# BopIt.net
KiCad netlist of a schematic drawn in Altium Designer
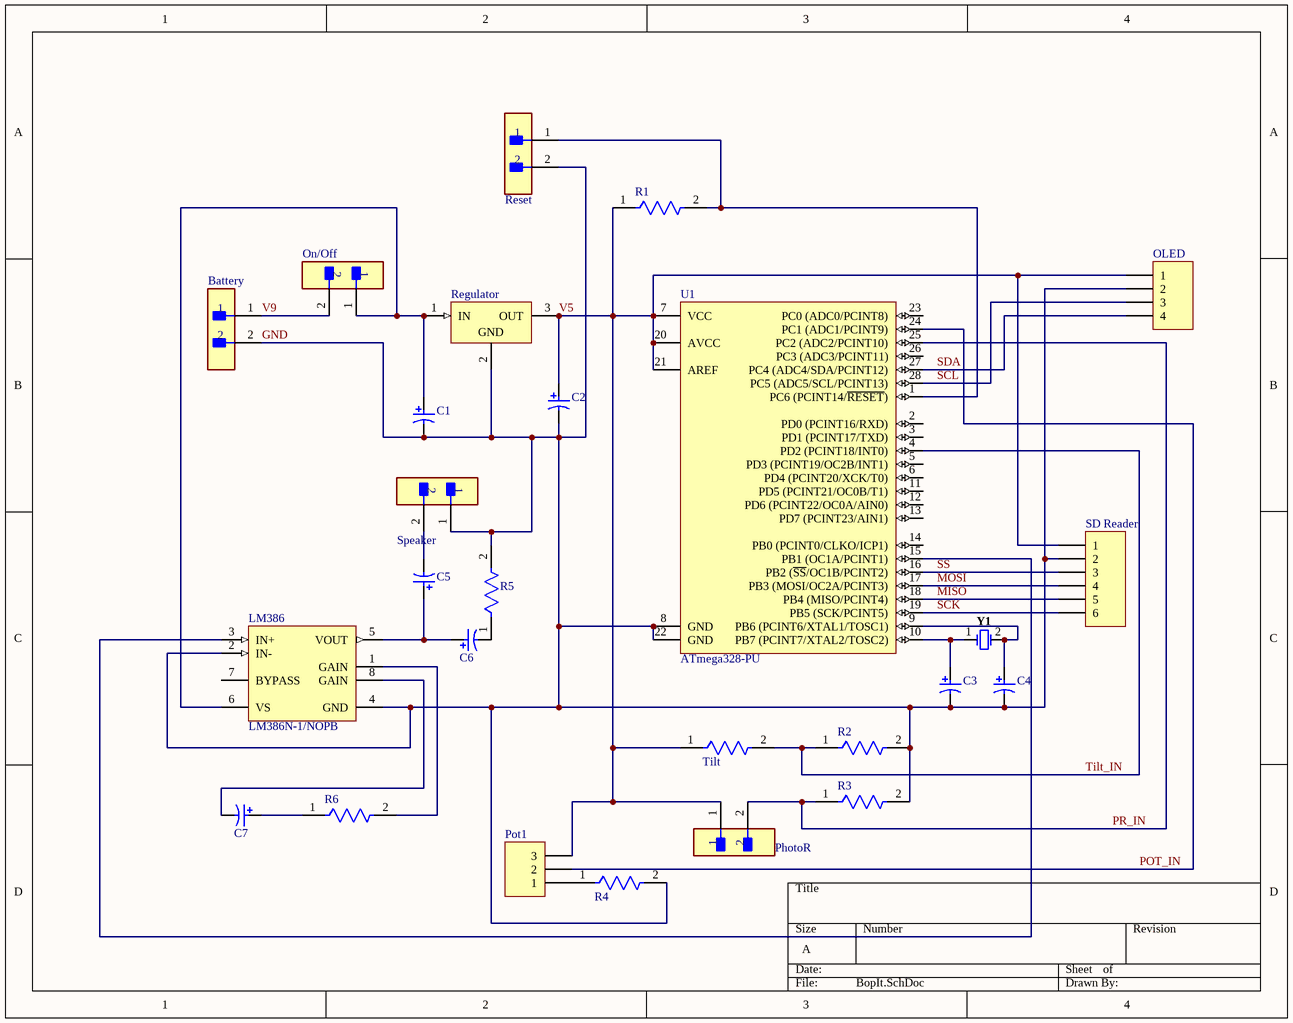
[diagram p0: BopIt.SchDoc]

(export (version "E")
  (design (tool "Eeschema 10.0.6"))
  (components
    (comp (ref "Battery")
      (value "M22-2510205")
      (footprint "FP-M22-2510205-MFG")
      (description "CONN HEADER VERT 2POS 2MM")
      (fields
        (field (name "MANUFACTURER") "Harwin")
        (field (name "OCTOPART") "https://octopart.com/m22-2510205-harwin-2538221")
      )
      (libsource (lib "") (part "3bc925449376181038e59eaffc5286c_2"))
    )
    (comp (ref "C1")
      (value "ECA1HM100")
      (footprint "CAPPR55-200-1100X500X1200")
      (description "Aluminum Electrolytic Capacitor, 10 uF, +/- 20%, 50 V, -40 to 85 degC, 2-Pin THD, RoHS, Bulk")
      (fields (field (name "MANUFACTURER") "Panasonic") (field (name "TOLERANCE") "20%"))
      (libsource (lib "Altium Content Vault") (part "CAP-P-2"))
    )
    (comp (ref "C2")
      (value "ECA1HM100")
      (footprint "CAPPR55-200-1100X500X1200")
      (description "Aluminum Electrolytic Capacitor, 10 uF, +/- 20%, 50 V, -40 to 85 degC, 2-Pin THD, RoHS, Bulk")
      (fields (field (name "MANUFACTURER") "Panasonic") (field (name "TOLERANCE") "20%"))
      (libsource (lib "Altium Content Vault") (part "CAP-P-2"))
    )
    (comp (ref "C3")
      (value "ECA1HM100")
      (footprint "CAPPR55-200-1100X500X1200")
      (description "Aluminum Electrolytic Capacitor, 10 uF, +/- 20%, 50 V, -40 to 85 degC, 2-Pin THD, RoHS, Bulk")
      (fields (field (name "MANUFACTURER") "Panasonic") (field (name "TOLERANCE") "20%"))
      (libsource (lib "Altium Content Vault") (part "CAP-P-2"))
    )
    (comp (ref "C4")
      (value "ECA1HM100")
      (footprint "CAPPR55-200-1100X500X1200")
      (description "Aluminum Electrolytic Capacitor, 10 uF, +/- 20%, 50 V, -40 to 85 degC, 2-Pin THD, RoHS, Bulk")
      (fields (field (name "MANUFACTURER") "Panasonic") (field (name "TOLERANCE") "20%"))
      (libsource (lib "Altium Content Vault") (part "CAP-P-2"))
    )
    (comp (ref "C5")
      (value "ECA-1VM221")
      (footprint "PNSC-ECA-1VM221-2")
      (description "Aluminum Electrolytic Capacitor, 220 uF, +/- 20%, 35 V, -40 to 85 degC, 2-Pin THD, RoHS, Bulk")
      (fields (field (name "MANUFACTURER") "Panasonic"))
      (libsource (lib "Altium Content Vault") (part "CAP-P-2"))
    )
    (comp (ref "C6")
      (value "ECA1HM100")
      (footprint "CAPPR55-200-1100X500X1200")
      (description "Aluminum Electrolytic Capacitor, 10 uF, +/- 20%, 50 V, -40 to 85 degC, 2-Pin THD, RoHS, Bulk")
      (fields (field (name "MANUFACTURER") "Panasonic") (field (name "TOLERANCE") "20%"))
      (libsource (lib "Altium Content Vault") (part "CAP-P-2"))
    )
    (comp (ref "C7")
      (value "ECA1HM100")
      (footprint "CAPPR55-200-1100X500X1200")
      (description "Aluminum Electrolytic Capacitor, 10 uF, +/- 20%, 50 V, -40 to 85 degC, 2-Pin THD, RoHS, Bulk")
      (fields (field (name "MANUFACTURER") "Panasonic") (field (name "TOLERANCE") "20%"))
      (libsource (lib "Altium Content Vault") (part "CAP-P-2"))
    )
    (comp (ref "LM386")
      (value "LM386N-1/NOPB")
      (footprint "P0008A")
      (description "Low Voltage Audio Power Amplifier, 8-pin MDIP, Pb-Free")
      (fields (field (name "MANUFACTURER") "Texas Instruments"))
      (libsource (lib "Altium Content Vault") (part "AMP-APA-LM386-8"))
    )
    (comp (ref "OLED")
      (value "~")
      (footprint "HDR1X4")
      (description "Header, 4-Pin")
      (fields (field (name "PUBLISHER") "Altium Limited"))
      (libsource (lib "Miscellaneous Connectors") (part "Header 4"))
    )
    (comp (ref "On/Off")
      (value "M22-2510205")
      (footprint "FP-M22-2510205-MFG")
      (description "CONN HEADER VERT 2POS 2MM")
      (fields
        (field (name "MANUFACTURER") "Harwin")
        (field (name "OCTOPART") "https://octopart.com/m22-2510205-harwin-2538221")
      )
      (libsource (lib "Altium Content Vault") (part "3bc925449376181038e59eaffc5286c"))
    )
    (comp (ref "PhotoR")
      (value "M22-2510205")
      (footprint "FP-M22-2510205-MFG")
      (description "CONN HEADER VERT 2POS 2MM")
      (fields
        (field (name "MANUFACTURER") "Harwin")
        (field (name "OCTOPART") "https://octopart.com/m22-2510205-harwin-2538221")
      )
      (libsource (lib "") (part "3bc925449376181038e59eaffc5286c_1"))
    )
    (comp (ref "Pot1")
      (value "Header 3")
      (footprint "HDR1X3")
      (description "Header, 3-Pin")
      (fields (field (name "PUBLISHER") "Altium Limited"))
      (libsource (lib "Miscellaneous Connectors") (part "Header 3"))
    )
    (comp (ref "R1")
      (value "CF18JT10K0")
      (footprint "FP-CF18-MFG")
      (description "RES 10K OHM 1/8W 5% CF AXIAL")
      (fields
        (field (name "MANUFACTURER") "Stackpole Electronics")
        (field (name "OCTOPART") "https://octopart.com/cf18jt10k0-stackpole+electronics-19205642")
      )
      (libsource (lib "Altium Content Vault") (part "1029c3af85768c4190bb7ad29bc67b5"))
    )
    (comp (ref "R2")
      (value "CF18JT10K0")
      (footprint "FP-CF18-MFG")
      (description "RES 10K OHM 1/8W 5% CF AXIAL")
      (fields
        (field (name "MANUFACTURER") "Stackpole Electronics")
        (field (name "OCTOPART") "https://octopart.com/cf18jt10k0-stackpole+electronics-19205642")
      )
      (libsource (lib "Altium Content Vault") (part "1029c3af85768c4190bb7ad29bc67b5"))
    )
    (comp (ref "R3")
      (value "CF18JT10K0")
      (footprint "FP-CF18-MFG")
      (description "RES 10K OHM 1/8W 5% CF AXIAL")
      (fields
        (field (name "MANUFACTURER") "Stackpole Electronics")
        (field (name "OCTOPART") "https://octopart.com/cf18jt10k0-stackpole+electronics-19205642")
      )
      (libsource (lib "Altium Content Vault") (part "1029c3af85768c4190bb7ad29bc67b5"))
    )
    (comp (ref "R4")
      (value "CF18JT10K0")
      (footprint "FP-CF18-MFG")
      (description "RES 10K OHM 1/8W 5% CF AXIAL")
      (fields
        (field (name "MANUFACTURER") "Stackpole Electronics")
        (field (name "OCTOPART") "https://octopart.com/cf18jt10k0-stackpole+electronics-19205642")
      )
      (libsource (lib "Altium Content Vault") (part "1029c3af85768c4190bb7ad29bc67b5"))
    )
    (comp (ref "R5")
      (value "CF18JT10K0")
      (footprint "FP-CF18-MFG")
      (description "RES 10K OHM 1/8W 5% CF AXIAL")
      (fields
        (field (name "MANUFACTURER") "Stackpole Electronics")
        (field (name "OCTOPART") "https://octopart.com/cf18jt10k0-stackpole+electronics-19205642")
      )
      (libsource (lib "Altium Content Vault") (part "1029c3af85768c4190bb7ad29bc67b5"))
    )
    (comp (ref "R6")
      (value "CF18JT10K0")
      (footprint "FP-CF18-MFG")
      (description "RES 10K OHM 1/8W 5% CF AXIAL")
      (fields
        (field (name "MANUFACTURER") "Stackpole Electronics")
        (field (name "OCTOPART") "https://octopart.com/cf18jt10k0-stackpole+electronics-19205642")
      )
      (libsource (lib "Altium Content Vault") (part "1029c3af85768c4190bb7ad29bc67b5"))
    )
    (comp (ref "Regulator")
      (value "LM7805CT")
      (footprint "FAIR-TO-220-3")
      (description "Positive Voltage Regulator, 5 V, 1 A, -40 to 125 degC, 3-Pin TO-220, RoHS, Tube")
      (fields (field (name "MANUFACTURER") "FairchildSemiconductor"))
      (libsource (lib "Altium Content Vault") (part "FAIR-LM7805CT-TO220-3"))
    )
    (comp (ref "Reset")
      (value "M22-2510205")
      (footprint "FP-M22-2510205-MFG")
      (description "CONN HEADER VERT 2POS 2MM")
      (fields
        (field (name "MANUFACTURER") "Harwin")
        (field (name "OCTOPART") "https://octopart.com/m22-2510205-harwin-2538221")
      )
      (libsource (lib "") (part "3bc925449376181038e59eaffc5286c_2"))
    )
    (comp (ref "SD Reader")
      (value "Header 6")
      (footprint "HDR1X6")
      (description "Header, 6-Pin")
      (fields (field (name "PUBLISHER") "Altium Limited"))
      (libsource (lib "Miscellaneous Connectors") (part "Header 6"))
    )
    (comp (ref "Speaker")
      (value "M22-2510205")
      (footprint "FP-M22-2510205-MFG")
      (description "CONN HEADER VERT 2POS 2MM")
      (fields
        (field (name "MANUFACTURER") "Harwin")
        (field (name "OCTOPART") "https://octopart.com/m22-2510205-harwin-2538221")
      )
      (libsource (lib "Altium Content Vault") (part "3bc925449376181038e59eaffc5286c"))
    )
    (comp (ref "Tilt")
      (value "CF18JT10K0")
      (footprint "FP-CF18-MFG")
      (description "RES 10K OHM 1/8W 5% CF AXIAL")
      (fields
        (field (name "MANUFACTURER") "Stackpole Electronics")
        (field (name "OCTOPART") "https://octopart.com/cf18jt10k0-stackpole+electronics-19205642")
      )
      (libsource (lib "Altium Content Vault") (part "1029c3af85768c4190bb7ad29bc67b5"))
    )
    (comp (ref "U1")
      (value "ATmega328-PU")
      (footprint "28P3")
      (libsource (lib "Altium Content Vault") (part "MC-8B-ATM48-IL28"))
    )
    (comp (ref "Y1")
      (value "FOXSLF/160-20")
      (footprint "FOX-FOXSLF160-20")
      (description "Resistance Weld Thru-Hole Crystal, 16 MHz, -20 to 70 degC, 2-Pin THD, RoHS, Bulk")
      (fields (field (name "TOLERANCE") "1%"))
      (libsource (lib "Altium Content Vault") (part "XTAL-1-2-2"))
    )
  )
  (nets
    (net (code "1") (name "/GND") (class "Default")
      (node (ref "Battery") (pin "2") (pinfunction "2_2") (pintype "passive"))
      (node (ref "C1") (pin "2") (pinfunction "2_2") (pintype "passive"))
      (node (ref "C2") (pin "2") (pinfunction "2_2") (pintype "passive"))
      (node (ref "C3") (pin "2") (pinfunction "2_2") (pintype "passive"))
      (node (ref "C4") (pin "2") (pinfunction "2_2") (pintype "passive"))
      (node (ref "LM386") (pin "2") (pinfunction "IN-_2") (pintype "input"))
      (node (ref "LM386") (pin "4") (pinfunction "GND_4") (pintype "power_in"))
      (node (ref "OLED") (pin "2") (pinfunction "2_2") (pintype "passive"))
      (node (ref "R2") (pin "2") (pinfunction "2_2") (pintype "passive"))
      (node (ref "R3") (pin "2") (pinfunction "2_2") (pintype "passive"))
      (node (ref "R4") (pin "2") (pinfunction "2_2") (pintype "passive"))
      (node (ref "R5") (pin "2") (pinfunction "2_2") (pintype "passive"))
      (node (ref "Regulator") (pin "2") (pinfunction "GND_2") (pintype "power_in"))
      (node (ref "Reset") (pin "2") (pinfunction "2_2") (pintype "passive"))
      (node (ref "SD Reader") (pin "2") (pinfunction "2_2") (pintype "passive"))
      (node (ref "Speaker") (pin "1") (pinfunction "1_1") (pintype "passive"))
      (node (ref "U1") (pin "22") (pinfunction "GND_22") (pintype "power_in"))
      (node (ref "U1") (pin "8") (pinfunction "GND_8") (pintype "power_in"))
    )
    (net (code "2") (name "/MISO") (class "Default")
      (node (ref "SD Reader") (pin "5") (pinfunction "5_5") (pintype "passive"))
      (node (ref "U1") (pin "18") (pinfunction "PB4_(MISO/PCINT4)_18") (pintype "bidirectional"))
    )
    (net (code "3") (name "/MOSI") (class "Default")
      (node (ref "SD Reader") (pin "4") (pinfunction "4_4") (pintype "passive"))
      (node (ref "U1") (pin "17") (pinfunction "PB3_(MOSI/OC2A/PCINT3)_17") (pintype "bidirectional"))
    )
    (net (code "4") (name "/POT_IN") (class "Default")
      (node (ref "Pot1") (pin "2") (pinfunction "2_2") (pintype "passive"))
      (node (ref "U1") (pin "24") (pinfunction "PC1_(ADC1/PCINT9)_24") (pintype "bidirectional"))
    )
    (net (code "5") (name "/PR_IN") (class "Default")
      (node (ref "PhotoR") (pin "2") (pinfunction "2_2") (pintype "passive"))
      (node (ref "R3") (pin "1") (pinfunction "1_1") (pintype "passive"))
      (node (ref "U1") (pin "25") (pinfunction "PC2_(ADC2/PCINT10)_25") (pintype "bidirectional"))
    )
    (net (code "6") (name "/SCK") (class "Default")
      (node (ref "SD Reader") (pin "6") (pinfunction "6_6") (pintype "passive"))
      (node (ref "U1") (pin "19") (pinfunction "PB5_(SCK/PCINT5)_19") (pintype "bidirectional"))
    )
    (net (code "7") (name "/SCL") (class "Default")
      (node (ref "OLED") (pin "3") (pinfunction "3_3") (pintype "passive"))
      (node (ref "U1") (pin "28") (pinfunction "PC5_(ADC5/SCL/PCINT13)_28") (pintype "bidirectional"))
    )
    (net (code "8") (name "/SDA") (class "Default")
      (node (ref "OLED") (pin "4") (pinfunction "4_4") (pintype "passive"))
      (node (ref "U1") (pin "27") (pinfunction "PC4_(ADC4/SDA/PCINT12)_27") (pintype "bidirectional"))
    )
    (net (code "9") (name "/SS") (class "Default")
      (node (ref "SD Reader") (pin "3") (pinfunction "3_3") (pintype "passive"))
      (node (ref "U1") (pin "16") (pinfunction "PB2_(~{SS}/OC1B/PCINT2)_16") (pintype "bidirectional"))
    )
    (net (code "10") (name "/Tilt_IN") (class "Default")
      (node (ref "R2") (pin "1") (pinfunction "1_1") (pintype "passive"))
      (node (ref "Tilt") (pin "2") (pinfunction "2_2") (pintype "passive"))
      (node (ref "U1") (pin "4") (pinfunction "PD2_(PCINT18/INT0)_4") (pintype "bidirectional"))
    )
    (net (code "11") (name "/V5") (class "Default")
      (node (ref "C2") (pin "1") (pinfunction "1_1") (pintype "passive"))
      (node (ref "OLED") (pin "1") (pinfunction "1_1") (pintype "passive"))
      (node (ref "PhotoR") (pin "1") (pinfunction "1_1") (pintype "passive"))
      (node (ref "Pot1") (pin "3") (pinfunction "3_3") (pintype "passive"))
      (node (ref "R1") (pin "1") (pinfunction "1_1") (pintype "passive"))
      (node (ref "Regulator") (pin "3") (pinfunction "OUT_3") (pintype "power_in"))
      (node (ref "SD Reader") (pin "1") (pinfunction "1_1") (pintype "passive"))
      (node (ref "Tilt") (pin "1") (pinfunction "1_1") (pintype "passive"))
      (node (ref "U1") (pin "20") (pinfunction "AVCC_20") (pintype "power_in"))
      (node (ref "U1") (pin "21") (pinfunction "AREF_21") (pintype "power_in"))
      (node (ref "U1") (pin "7") (pinfunction "VCC_7") (pintype "power_in"))
    )
    (net (code "12") (name "/V9") (class "Default")
      (node (ref "Battery") (pin "1") (pinfunction "1_1") (pintype "passive"))
      (node (ref "On/Off") (pin "2") (pinfunction "2_2") (pintype "passive"))
    )
    (net (code "13") (name "Net-(C5-Pad2)") (class "Default")
      (node (ref "C5") (pin "2") (pinfunction "2_2") (pintype "passive"))
      (node (ref "Speaker") (pin "2") (pinfunction "2_2") (pintype "passive"))
    )
    (net (code "14") (name "Net-(C6-Pad2)") (class "Default")
      (node (ref "C6") (pin "2") (pinfunction "2_2") (pintype "passive"))
      (node (ref "R5") (pin "1") (pinfunction "1_1") (pintype "passive"))
    )
    (net (code "15") (name "Net-(C7-Pad1)") (class "Default")
      (node (ref "C7") (pin "1") (pinfunction "1_1") (pintype "passive"))
      (node (ref "R6") (pin "1") (pinfunction "1_1") (pintype "passive"))
    )
    (net (code "16") (name "Net-(C7-Pad2)") (class "Default")
      (node (ref "C7") (pin "2") (pinfunction "2_2") (pintype "passive"))
      (node (ref "LM386") (pin "8") (pinfunction "GAIN_8") (pintype "passive"))
    )
    (net (code "17") (name "Net-(LM386-GAIN-Pad1)") (class "Default")
      (node (ref "LM386") (pin "1") (pinfunction "GAIN_1") (pintype "passive"))
      (node (ref "R6") (pin "2") (pinfunction "2_2") (pintype "passive"))
    )
    (net (code "18") (name "Net-(LM386-IN+)") (class "Default")
      (node (ref "LM386") (pin "3") (pinfunction "IN+_3") (pintype "input"))
      (node (ref "U1") (pin "15") (pinfunction "PB1_(OC1A/PCINT1)_15") (pintype "bidirectional"))
    )
    (net (code "19") (name "Net-(LM386-VOUT)") (class "Default")
      (node (ref "C5") (pin "1") (pinfunction "1_1") (pintype "passive"))
      (node (ref "C6") (pin "1") (pinfunction "1_1") (pintype "passive"))
      (node (ref "LM386") (pin "5") (pinfunction "VOUT_5") (pintype "output"))
    )
    (net (code "20") (name "Net-(LM386-VS)") (class "Default")
      (node (ref "C1") (pin "1") (pinfunction "1_1") (pintype "passive"))
      (node (ref "LM386") (pin "6") (pinfunction "VS_6") (pintype "power_in"))
      (node (ref "On/Off") (pin "1") (pinfunction "1_1") (pintype "passive"))
      (node (ref "Regulator") (pin "1") (pinfunction "IN_1") (pintype "input"))
    )
    (net (code "21") (name "Net-(Pot1-Pad1)") (class "Default")
      (node (ref "Pot1") (pin "1") (pinfunction "1_1") (pintype "passive"))
      (node (ref "R4") (pin "1") (pinfunction "1_1") (pintype "passive"))
    )
    (net (code "22") (name "Net-(U1-PB6_(PCINT6{slash}XTAL1{slash}TOSC1))") (class "Default")
      (node (ref "C4") (pin "1") (pinfunction "1_1") (pintype "passive"))
      (node (ref "U1") (pin "9") (pinfunction "PB6_(PCINT6/XTAL1/TOSC1)_9") (pintype "bidirectional"))
      (node (ref "Y1") (pin "2") (pinfunction "2_2") (pintype "passive"))
    )
    (net (code "23") (name "Net-(U1-PB7_(PCINT7{slash}XTAL2{slash}TOSC2))") (class "Default")
      (node (ref "C3") (pin "1") (pinfunction "1_1") (pintype "passive"))
      (node (ref "U1") (pin "10") (pinfunction "PB7_(PCINT7/XTAL2/TOSC2)_10") (pintype "bidirectional"))
      (node (ref "Y1") (pin "1") (pinfunction "1_1") (pintype "passive"))
    )
    (net (code "24") (name "Net-(U1-PC6_(PCINT14{slash}~{RESET}))") (class "Default")
      (node (ref "R1") (pin "2") (pinfunction "2_2") (pintype "passive"))
      (node (ref "Reset") (pin "1") (pinfunction "1_1") (pintype "passive"))
      (node (ref "U1") (pin "1") (pinfunction "PC6_(PCINT14/~{RESET})_1") (pintype "bidirectional"))
    )
    (net (code "25") (name "unconnected-(LM386-BYPASS-Pad7)") (class "Default")
      (node (ref "LM386") (pin "7") (pinfunction "BYPASS_7") (pintype "passive"))
    )
    (net (code "26") (name "unconnected-(U1-PB0_(PCINT0{slash}CLKO{slash}ICP1)-Pad14)") (class "Default")
      (node (ref "U1") (pin "14") (pinfunction "PB0_(PCINT0/CLKO/ICP1)_14") (pintype "bidirectional"))
    )
    (net (code "27") (name "unconnected-(U1-PC0_(ADC0{slash}PCINT8)-Pad23)") (class "Default")
      (node (ref "U1") (pin "23") (pinfunction "PC0_(ADC0/PCINT8)_23") (pintype "bidirectional"))
    )
    (net (code "28") (name "unconnected-(U1-PC3_(ADC3{slash}PCINT11)-Pad26)") (class "Default")
      (node (ref "U1") (pin "26") (pinfunction "PC3_(ADC3/PCINT11)_26") (pintype "bidirectional"))
    )
    (net (code "29") (name "unconnected-(U1-PD0_(PCINT16{slash}RXD)-Pad2)") (class "Default")
      (node (ref "U1") (pin "2") (pinfunction "PD0_(PCINT16/RXD)_2") (pintype "bidirectional"))
    )
    (net (code "30") (name "unconnected-(U1-PD1_(PCINT17{slash}TXD)-Pad3)") (class "Default")
      (node (ref "U1") (pin "3") (pinfunction "PD1_(PCINT17/TXD)_3") (pintype "bidirectional"))
    )
    (net (code "31") (name "unconnected-(U1-PD3_(PCINT19{slash}OC2B{slash}INT1)-Pad5)") (class "Default")
      (node (ref "U1") (pin "5") (pinfunction "PD3_(PCINT19/OC2B/INT1)_5") (pintype "bidirectional"))
    )
    (net (code "32") (name "unconnected-(U1-PD4_(PCINT20{slash}XCK{slash}T0)-Pad6)") (class "Default")
      (node (ref "U1") (pin "6") (pinfunction "PD4_(PCINT20/XCK/T0)_6") (pintype "bidirectional"))
    )
    (net (code "33") (name "unconnected-(U1-PD5_(PCINT21{slash}OC0B{slash}T1)-Pad11)") (class "Default")
      (node (ref "U1") (pin "11") (pinfunction "PD5_(PCINT21/OC0B/T1)_11") (pintype "bidirectional"))
    )
    (net (code "34") (name "unconnected-(U1-PD6_(PCINT22{slash}OC0A{slash}AIN0)-Pad12)") (class "Default")
      (node (ref "U1") (pin "12") (pinfunction "PD6_(PCINT22/OC0A/AIN0)_12") (pintype "bidirectional"))
    )
    (net (code "35") (name "unconnected-(U1-PD7_(PCINT23{slash}AIN1)-Pad13)") (class "Default")
      (node (ref "U1") (pin "13") (pinfunction "PD7_(PCINT23/AIN1)_13") (pintype "bidirectional"))
    )
  )
)
